# STM32_miniSystem.net
KiCad netlist of a schematic drawn in Altium Designer
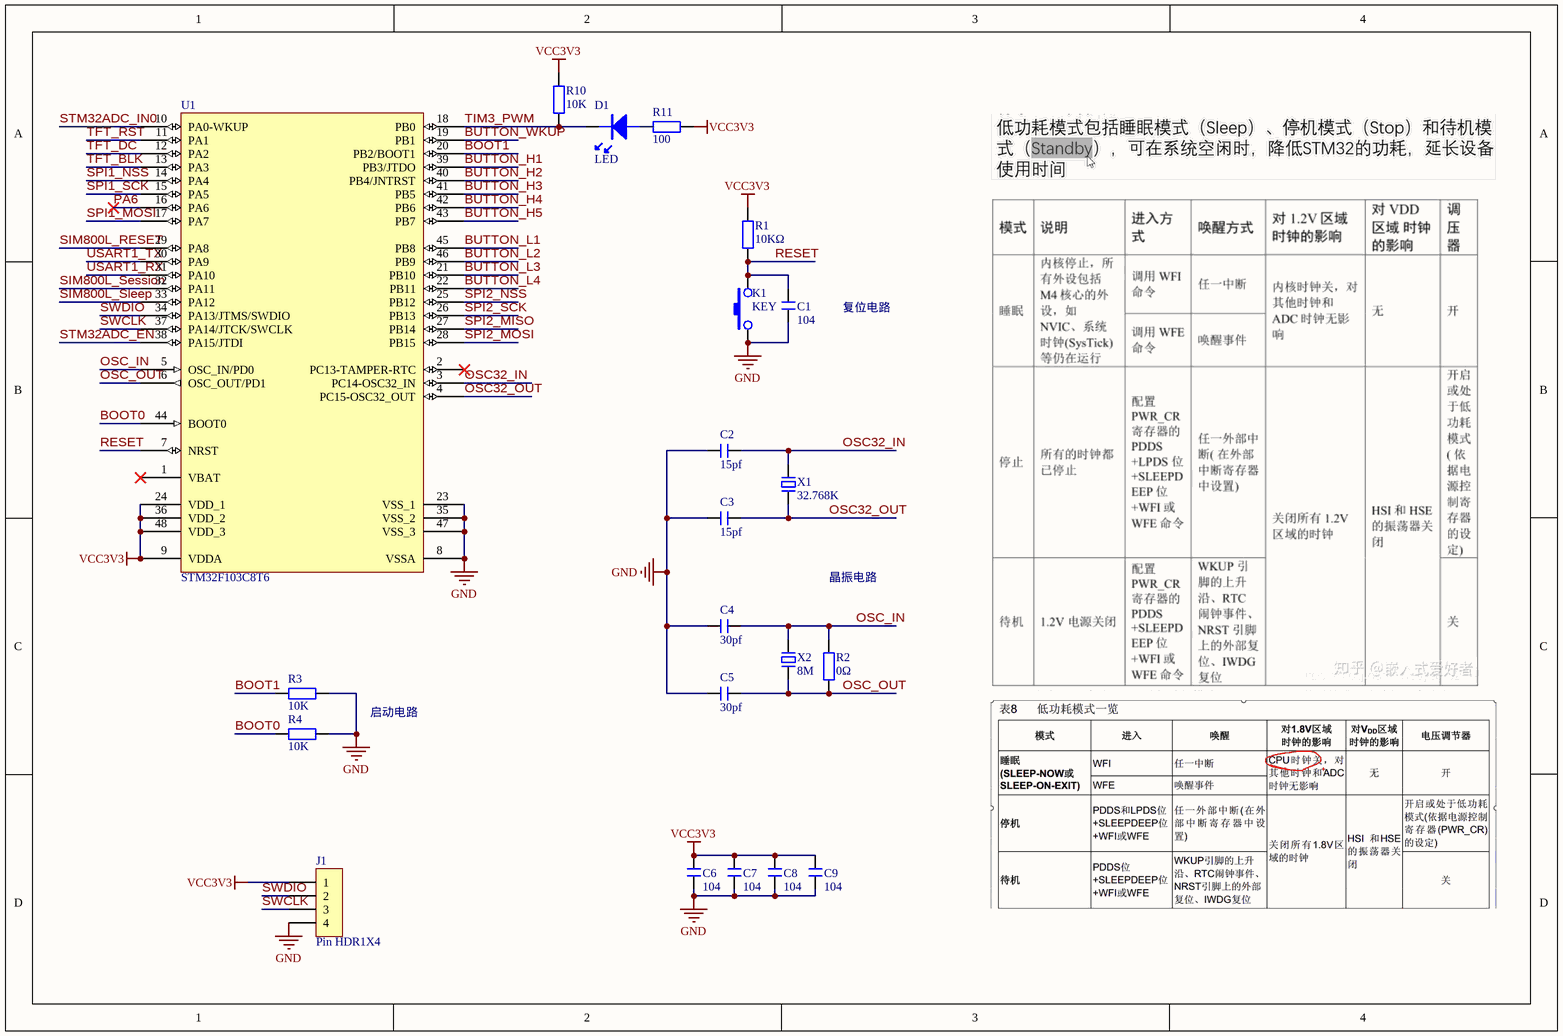
[diagram p0: STM32_miniSystem.SchDoc]

(export (version "E")
  (design (tool "Eeschema 10.0.6"))
  (components
    (comp (ref "C1")
      (value "104")
      (footprint "C 0805_L")
      (description "无极性贴片电容")
      (fields (field (name "版权归属") "源创客"))
      (libsource (lib "3.1   - 电阻-电容-电感") (part "C"))
    )
    (comp (ref "C2")
      (value "15pf")
      (footprint "CC 1.8*3.6")
      (description "直插瓷片电容")
      (fields (field (name "版权归属") "源创客"))
      (libsource (lib "STM32Project_1") (part "C-CC_1"))
    )
    (comp (ref "C3")
      (value "15pf")
      (footprint "CC 1.8*3.6")
      (description "直插瓷片电容")
      (fields (field (name "版权归属") "源创客"))
      (libsource (lib "STM32Project_1") (part "C-CC_1"))
    )
    (comp (ref "C4")
      (value "30pf")
      (footprint "CC 1.8*3.6")
      (description "直插瓷片电容")
      (fields (field (name "版权归属") "源创客"))
      (libsource (lib "STM32Project_1") (part "C-CC_2"))
    )
    (comp (ref "C5")
      (value "30pf")
      (footprint "CC 1.8*3.6")
      (description "直插瓷片电容")
      (fields (field (name "版权归属") "源创客"))
      (libsource (lib "STM32Project_1") (part "C-CC_2"))
    )
    (comp (ref "C6")
      (value "104")
      (footprint "C 0805_L")
      (description "无极性贴片电容")
      (fields (field (name "版权归属") "源创客"))
      (libsource (lib "3.1   - 电阻-电容-电感") (part "C"))
    )
    (comp (ref "C7")
      (value "104")
      (footprint "C 0805_L")
      (description "无极性贴片电容")
      (fields (field (name "版权归属") "源创客"))
      (libsource (lib "3.1   - 电阻-电容-电感") (part "C"))
    )
    (comp (ref "C8")
      (value "104")
      (footprint "C 0805_L")
      (description "无极性贴片电容")
      (fields (field (name "版权归属") "源创客"))
      (libsource (lib "3.1   - 电阻-电容-电感") (part "C"))
    )
    (comp (ref "C9")
      (value "104")
      (footprint "C 0805_L")
      (description "无极性贴片电容")
      (fields (field (name "版权归属") "源创客"))
      (libsource (lib "3.1   - 电阻-电容-电感") (part "C"))
    )
    (comp (ref "D1") (value "LED") (footprint "LED-0603G") (libsource (lib "STM32Project_1") (part "LED")))
    (comp (ref "J1")
      (value "Pin HDR1X4")
      (footprint "Pin HDR1X4/2.54mm-W")
      (libsource (lib "STM32Project_1") (part "Pin HDR1X4"))
    )
    (comp (ref "K1") (value "KEY") (footprint "DIP-12X12X6") (libsource (lib "STM32Project_1") (part "KEY")))
    (comp (ref "R1")
      (value "10KΩ")
      (footprint "R 0805_L")
      (description "贴片电阻")
      (fields (field (name "版权归属") "源创客"))
      (libsource (lib "STM32Project_1") (part "R"))
    )
    (comp (ref "R2")
      (value "0Ω")
      (footprint "R 0805_L")
      (description "贴片电阻")
      (fields (field (name "版权归属") "源创客"))
      (libsource (lib "STM32Project_1") (part "R"))
    )
    (comp (ref "R3")
      (value "10K")
      (footprint "R 0805_L")
      (description "贴片电阻")
      (fields (field (name "版权归属") "源创客"))
      (libsource (lib "STM32Project_1") (part "R_3"))
    )
    (comp (ref "R4")
      (value "10K")
      (footprint "R 0805_L")
      (description "贴片电阻")
      (fields (field (name "版权归属") "源创客"))
      (libsource (lib "STM32Project_1") (part "R_3"))
    )
    (comp (ref "R10")
      (value "10K")
      (footprint "R 0805_L")
      (description "贴片电阻")
      (fields (field (name "版权归属") "源创客"))
      (libsource (lib "STM32Project_1") (part "R_3"))
    )
    (comp (ref "R11")
      (value "100")
      (footprint "R 0805_L")
      (description "贴片电阻")
      (fields (field (name "版权归属") "源创客"))
      (libsource (lib "STM32Project_1") (part "R_2"))
    )
    (comp (ref "U1")
      (value "STM32F103C8T6")
      (footprint "LQFP48 7X7")
      (libsource (lib "STM32Project_1") (part "STM32F103C8T6"))
    )
    (comp (ref "X1")
      (value "32.768K")
      (footprint "OSC-3x10-WI-B")
      (description "32.768K_2脚无源脚晶振")
      (libsource (lib "STM32Project_1") (part "XTAL-2P"))
    )
    (comp (ref "X2")
      (value "8M")
      (footprint "OSC HC-49S")
      (description "8M_2脚无源脚晶振")
      (libsource (lib "STM32Project_1") (part "XTAL-2P_1"))
    )
  )
  (nets
    (net (code "1") (name "/BOOT0") (class "Default")
      (node (ref "R4") (pin "2") (pinfunction "2_2") (pintype "passive"))
      (node (ref "U1") (pin "44") (pinfunction "BOOT0_44") (pintype "input"))
    )
    (net (code "2") (name "/BOOT1") (class "Default")
      (node (ref "R3") (pin "1") (pinfunction "1_1") (pintype "passive"))
      (node (ref "U1") (pin "20") (pinfunction "PB2/BOOT1_20") (pintype "bidirectional"))
    )
    (net (code "3") (name "/BUTTON_H1") (class "Default")
      (node (ref "U1") (pin "39") (pinfunction "PB3/JTDO_39") (pintype "bidirectional"))
    )
    (net (code "4") (name "/BUTTON_H2") (class "Default")
      (node (ref "U1") (pin "40") (pinfunction "PB4/JNTRST_40") (pintype "bidirectional"))
    )
    (net (code "5") (name "/BUTTON_H3") (class "Default")
      (node (ref "U1") (pin "41") (pinfunction "PB5_41") (pintype "bidirectional"))
    )
    (net (code "6") (name "/BUTTON_H4") (class "Default")
      (node (ref "U1") (pin "42") (pinfunction "PB6_42") (pintype "bidirectional"))
    )
    (net (code "7") (name "/BUTTON_H5") (class "Default")
      (node (ref "U1") (pin "43") (pinfunction "PB7_43") (pintype "bidirectional"))
    )
    (net (code "8") (name "/BUTTON_L1") (class "Default")
      (node (ref "U1") (pin "45") (pinfunction "PB8_45") (pintype "bidirectional"))
    )
    (net (code "9") (name "/BUTTON_L2") (class "Default")
      (node (ref "U1") (pin "46") (pinfunction "PB9_46") (pintype "bidirectional"))
    )
    (net (code "10") (name "/BUTTON_L3") (class "Default")
      (node (ref "U1") (pin "21") (pinfunction "PB10_21") (pintype "bidirectional"))
    )
    (net (code "11") (name "/BUTTON_L4") (class "Default")
      (node (ref "U1") (pin "22") (pinfunction "PB11_22") (pintype "bidirectional"))
    )
    (net (code "12") (name "/BUTTON_WKUP") (class "Default")
      (node (ref "U1") (pin "19") (pinfunction "PB1_19") (pintype "bidirectional"))
    )
    (net (code "13") (name "/OSC32_IN") (class "Default")
      (node (ref "C2") (pin "2") (pinfunction "2_2") (pintype "passive"))
      (node (ref "U1") (pin "3") (pinfunction "PC14-OSC32_IN_3") (pintype "bidirectional"))
      (node (ref "X1") (pin "2") (pinfunction "2_2") (pintype "passive"))
    )
    (net (code "14") (name "/OSC32_OUT") (class "Default")
      (node (ref "C3") (pin "2") (pinfunction "2_2") (pintype "passive"))
      (node (ref "U1") (pin "4") (pinfunction "PC15-OSC32_OUT_4") (pintype "bidirectional"))
      (node (ref "X1") (pin "1") (pinfunction "1_1") (pintype "passive"))
    )
    (net (code "15") (name "/OSC_IN") (class "Default")
      (node (ref "C4") (pin "2") (pinfunction "2_2") (pintype "passive"))
      (node (ref "R2") (pin "2") (pinfunction "2_2") (pintype "passive"))
      (node (ref "U1") (pin "5") (pinfunction "OSC_IN/PD0_5") (pintype "input"))
      (node (ref "X2") (pin "2") (pinfunction "2_2") (pintype "passive"))
    )
    (net (code "16") (name "/OSC_OUT") (class "Default")
      (node (ref "C5") (pin "2") (pinfunction "2_2") (pintype "passive"))
      (node (ref "R2") (pin "1") (pinfunction "1_1") (pintype "passive"))
      (node (ref "U1") (pin "6") (pinfunction "OSC_OUT/PD1_6") (pintype "output"))
      (node (ref "X2") (pin "1") (pinfunction "1_1") (pintype "passive"))
    )
    (net (code "17") (name "/PA6") (class "Default")
      (node (ref "U1") (pin "16") (pinfunction "PA6_16") (pintype "bidirectional+no_connect"))
    )
    (net (code "18") (name "/RESET") (class "Default")
      (node (ref "C1") (pin "2") (pinfunction "2_2") (pintype "passive"))
      (node (ref "K1") (pin "3") (pinfunction "3_3") (pintype "passive"))
      (node (ref "R1") (pin "1") (pinfunction "1_1") (pintype "passive"))
      (node (ref "U1") (pin "7") (pinfunction "NRST_7") (pintype "bidirectional"))
    )
    (net (code "19") (name "/SIM800L_RESET") (class "Default")
      (node (ref "U1") (pin "29") (pinfunction "PA8_29") (pintype "bidirectional"))
    )
    (net (code "20") (name "/SIM800L_Session") (class "Default")
      (node (ref "U1") (pin "32") (pinfunction "PA11_32") (pintype "bidirectional"))
    )
    (net (code "21") (name "/SIM800L_Sleep") (class "Default")
      (node (ref "U1") (pin "33") (pinfunction "PA12_33") (pintype "bidirectional"))
    )
    (net (code "22") (name "/SPI1_MOSI") (class "Default")
      (node (ref "U1") (pin "17") (pinfunction "PA7_17") (pintype "bidirectional"))
    )
    (net (code "23") (name "/SPI1_NSS") (class "Default")
      (node (ref "U1") (pin "14") (pinfunction "PA4_14") (pintype "bidirectional"))
    )
    (net (code "24") (name "/SPI1_SCK") (class "Default")
      (node (ref "U1") (pin "15") (pinfunction "PA5_15") (pintype "bidirectional"))
    )
    (net (code "25") (name "/SPI2_MISO") (class "Default")
      (node (ref "U1") (pin "27") (pinfunction "PB14_27") (pintype "bidirectional"))
    )
    (net (code "26") (name "/SPI2_MOSI") (class "Default")
      (node (ref "U1") (pin "28") (pinfunction "PB15_28") (pintype "bidirectional"))
    )
    (net (code "27") (name "/SPI2_NSS") (class "Default")
      (node (ref "U1") (pin "25") (pinfunction "PB12_25") (pintype "bidirectional"))
    )
    (net (code "28") (name "/SPI2_SCK") (class "Default")
      (node (ref "U1") (pin "26") (pinfunction "PB13_26") (pintype "bidirectional"))
    )
    (net (code "29") (name "/STM32ADC_EN") (class "Default")
      (node (ref "U1") (pin "38") (pinfunction "PA15/JTDI_38") (pintype "bidirectional"))
    )
    (net (code "30") (name "/STM32ADC_IN0") (class "Default")
      (node (ref "U1") (pin "10") (pinfunction "PA0-WKUP_10") (pintype "bidirectional"))
    )
    (net (code "31") (name "/SWCLK") (class "Default")
      (node (ref "J1") (pin "3") (pinfunction "3_3") (pintype "passive"))
      (node (ref "U1") (pin "37") (pinfunction "PA14/JTCK/SWCLK_37") (pintype "bidirectional"))
    )
    (net (code "32") (name "/SWDIO") (class "Default")
      (node (ref "J1") (pin "2") (pinfunction "2_2") (pintype "passive"))
      (node (ref "U1") (pin "34") (pinfunction "PA13/JTMS/SWDIO_34") (pintype "bidirectional"))
    )
    (net (code "33") (name "/TFT_BLK") (class "Default")
      (node (ref "U1") (pin "13") (pinfunction "PA3_13") (pintype "bidirectional"))
    )
    (net (code "34") (name "/TFT_DC") (class "Default")
      (node (ref "U1") (pin "12") (pinfunction "PA2_12") (pintype "bidirectional"))
    )
    (net (code "35") (name "/TFT_RST") (class "Default")
      (node (ref "U1") (pin "11") (pinfunction "PA1_11") (pintype "bidirectional"))
    )
    (net (code "36") (name "/TIM3_PWM") (class "Default")
      (node (ref "D1") (pin "K") (pinfunction "K_K") (pintype "passive"))
      (node (ref "R10") (pin "1") (pinfunction "1_1") (pintype "passive"))
      (node (ref "U1") (pin "18") (pinfunction "PB0_18") (pintype "bidirectional"))
    )
    (net (code "37") (name "/USART1_RX") (class "Default")
      (node (ref "U1") (pin "31") (pinfunction "PA10_31") (pintype "bidirectional"))
    )
    (net (code "38") (name "/USART1_TX") (class "Default")
      (node (ref "U1") (pin "30") (pinfunction "PA9_30") (pintype "bidirectional"))
    )
    (net (code "39") (name "GND") (class "Default")
      (node (ref "C1") (pin "1") (pinfunction "1_1") (pintype "passive"))
      (node (ref "C2") (pin "1") (pinfunction "1_1") (pintype "passive"))
      (node (ref "C3") (pin "1") (pinfunction "1_1") (pintype "passive"))
      (node (ref "C4") (pin "1") (pinfunction "1_1") (pintype "passive"))
      (node (ref "C5") (pin "1") (pinfunction "1_1") (pintype "passive"))
      (node (ref "C6") (pin "1") (pinfunction "1_1") (pintype "passive"))
      (node (ref "C7") (pin "1") (pinfunction "1_1") (pintype "passive"))
      (node (ref "C8") (pin "1") (pinfunction "1_1") (pintype "passive"))
      (node (ref "C9") (pin "1") (pinfunction "1_1") (pintype "passive"))
      (node (ref "J1") (pin "4") (pinfunction "4_4") (pintype "passive"))
      (node (ref "K1") (pin "1") (pinfunction "1_1") (pintype "passive"))
      (node (ref "R3") (pin "2") (pinfunction "2_2") (pintype "passive"))
      (node (ref "R4") (pin "1") (pinfunction "1_1") (pintype "passive"))
      (node (ref "U1") (pin "23") (pinfunction "VSS_1_23") (pintype "power_in"))
      (node (ref "U1") (pin "35") (pinfunction "VSS_2_35") (pintype "power_in"))
      (node (ref "U1") (pin "47") (pinfunction "VSS_3_47") (pintype "power_in"))
      (node (ref "U1") (pin "8") (pinfunction "VSSA_8") (pintype "power_in"))
    )
    (net (code "40") (name "Net-(D1-PadA)") (class "Default")
      (node (ref "D1") (pin "A") (pinfunction "A_A") (pintype "passive"))
      (node (ref "R11") (pin "1") (pinfunction "1_1") (pintype "passive"))
    )
    (net (code "41") (name "VCC3V3") (class "Default")
      (node (ref "C6") (pin "2") (pinfunction "2_2") (pintype "passive"))
      (node (ref "C7") (pin "2") (pinfunction "2_2") (pintype "passive"))
      (node (ref "C8") (pin "2") (pinfunction "2_2") (pintype "passive"))
      (node (ref "C9") (pin "2") (pinfunction "2_2") (pintype "passive"))
      (node (ref "J1") (pin "1") (pinfunction "1_1") (pintype "passive"))
      (node (ref "R1") (pin "2") (pinfunction "2_2") (pintype "passive"))
      (node (ref "R10") (pin "2") (pinfunction "2_2") (pintype "passive"))
      (node (ref "R11") (pin "2") (pinfunction "2_2") (pintype "passive"))
      (node (ref "U1") (pin "24") (pinfunction "VDD_1_24") (pintype "power_in"))
      (node (ref "U1") (pin "36") (pinfunction "VDD_2_36") (pintype "power_in"))
      (node (ref "U1") (pin "48") (pinfunction "VDD_3_48") (pintype "power_in"))
      (node (ref "U1") (pin "9") (pinfunction "VDDA_9") (pintype "power_in"))
    )
    (net (code "42") (name "unconnected-(U1-PC13-TAMPER-RTC-Pad2)") (class "Default")
      (node (ref "U1") (pin "2") (pinfunction "PC13-TAMPER-RTC_2") (pintype "bidirectional+no_connect"))
    )
    (net (code "43") (name "unconnected-(U1-VBAT-Pad1)") (class "Default")
      (node (ref "U1") (pin "1") (pinfunction "VBAT_1") (pintype "power_in+no_connect"))
    )
  )
)
